# PMOD_ARD_RASP.net
KiCad netlist of a schematic drawn in Altium Designer
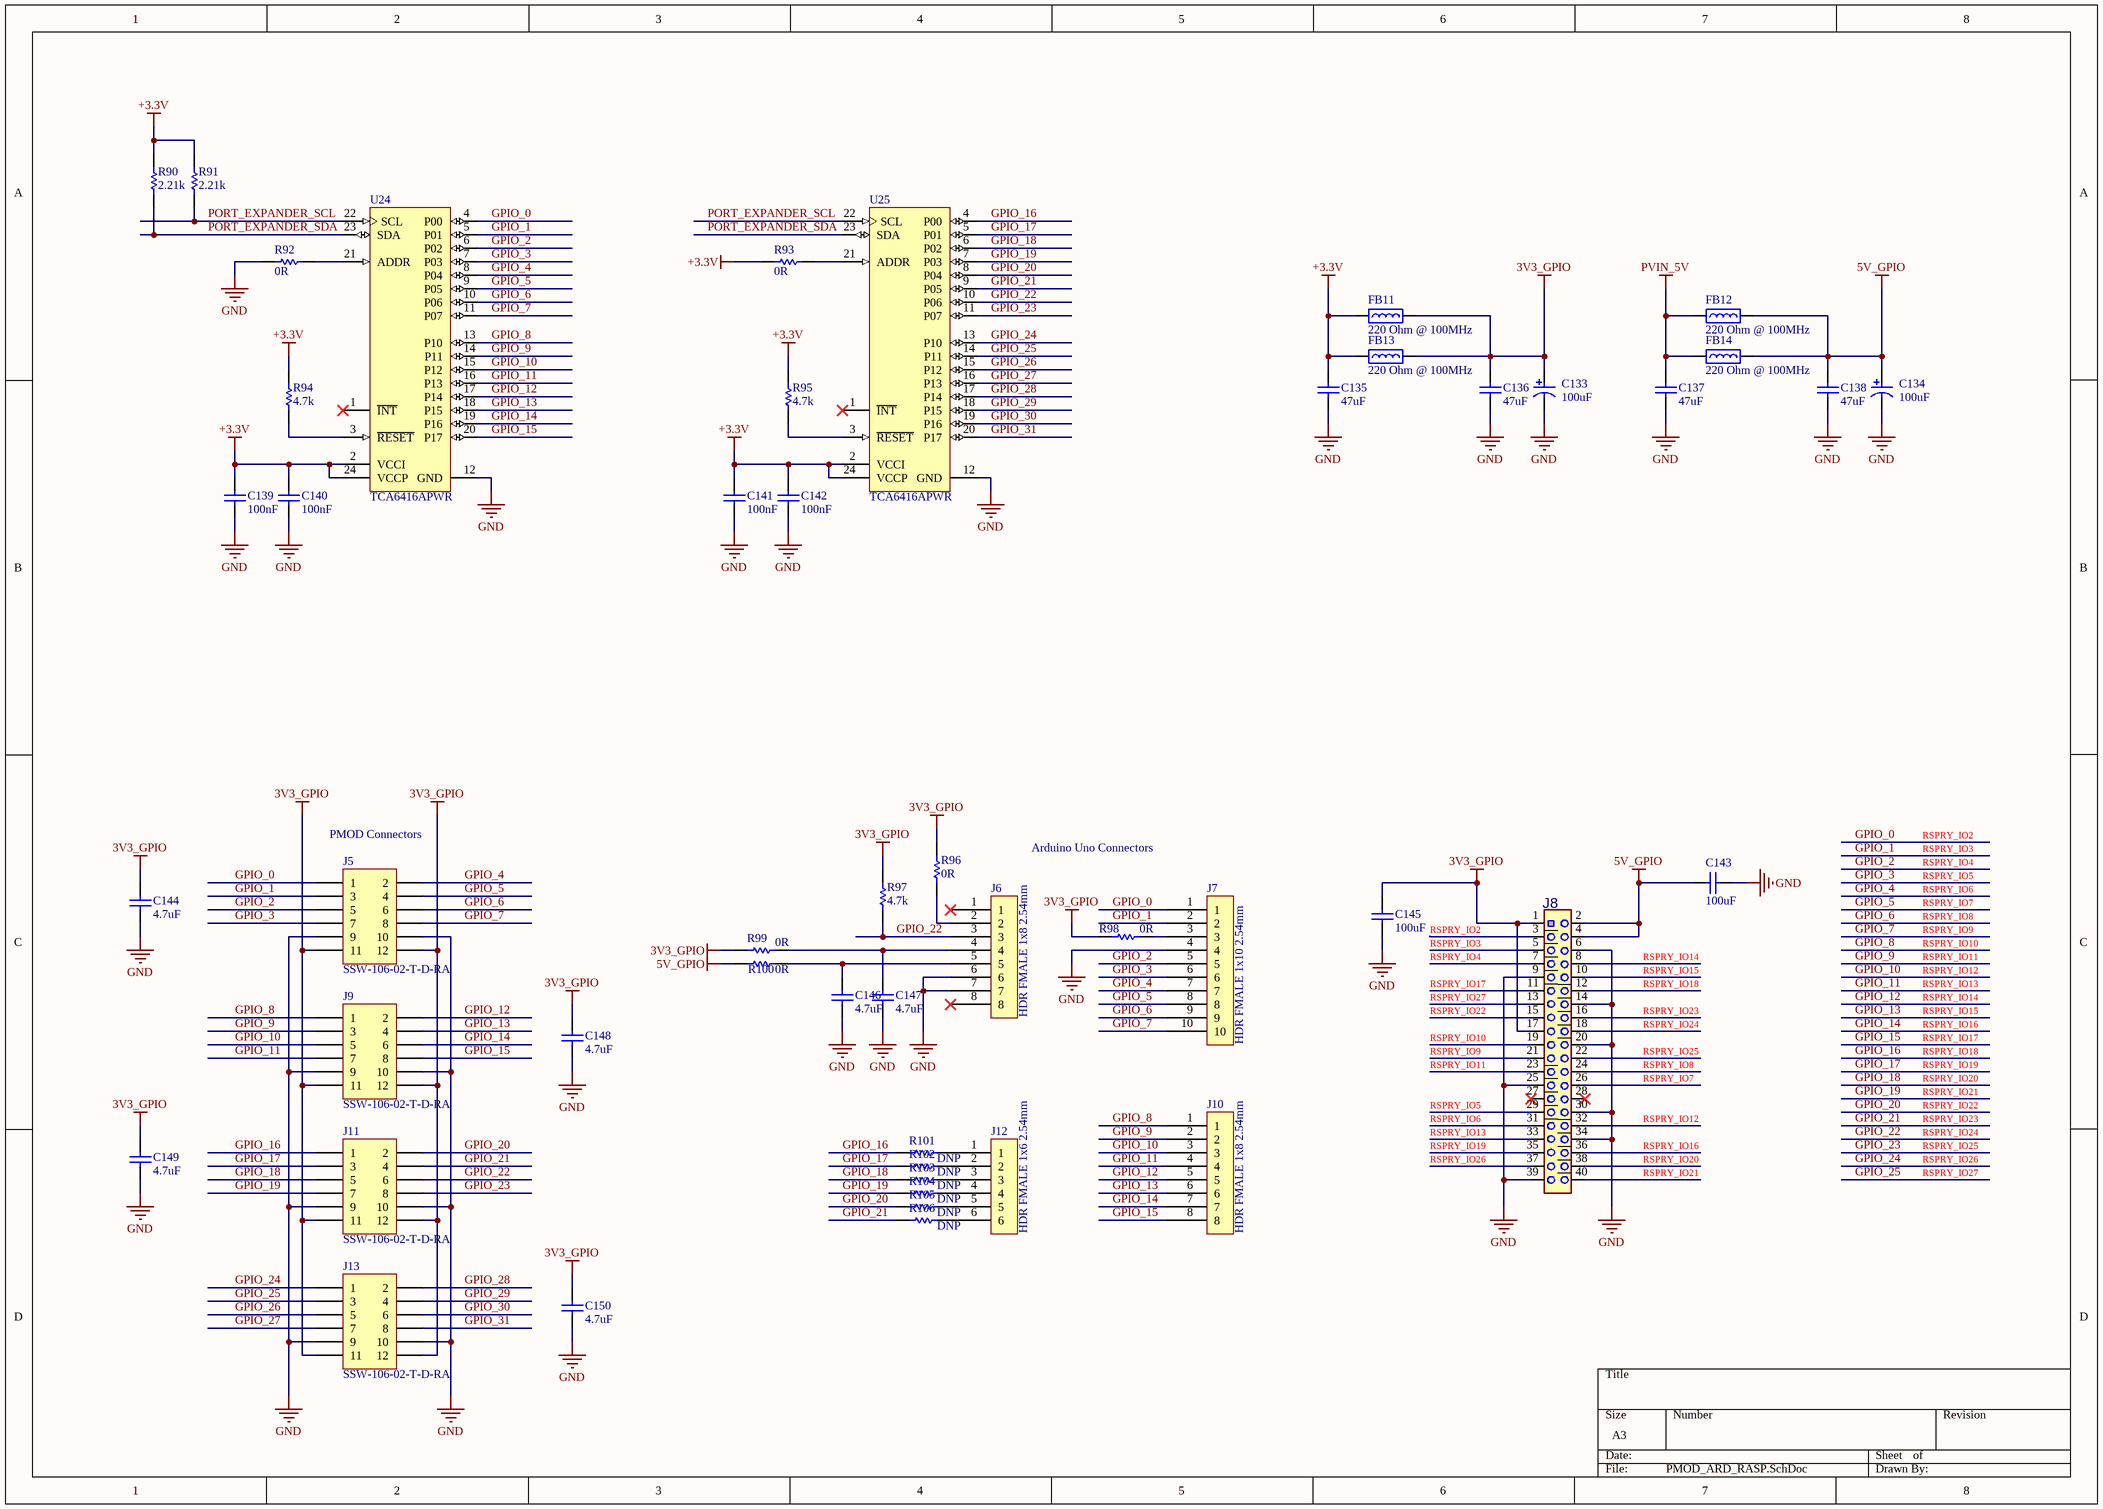
[diagram p0: PMOD_ARD_RASP.SchDoc]

(export (version "E")
  (design (tool "Eeschema 10.0.6"))
  (components
    (comp (ref "C133")
      (value "100uF")
      (footprint "AVX_TAN_F95_P_0905")
      (description "CAP TANT 100UF 6.3V 20% 0805")
      (fields (field (name "VOLTAGE") "6.3V") (field (name "TOLERANCE") "20%"))
      (libsource (lib "Ultrascale_SchLib") (part "CAPELE0905TAN100U6V3_20T"))
    )
    (comp (ref "C134")
      (value "100uF")
      (footprint "AVX_TAN_F95_P_0905")
      (description "CAP TANT 100UF 6.3V 20% 0805")
      (fields (field (name "VOLTAGE") "6.3V") (field (name "TOLERANCE") "20%"))
      (libsource (lib "Ultrascale_SchLib") (part "CAPELE0905TAN100U6V3_20T"))
    )
    (comp (ref "C135")
      (value "47uF")
      (footprint "CAPC3216L_1206")
      (description "CAP CER 47UF 25V X5R 1206")
      (fields (field (name "VOLTAGE") "25V") (field (name "TOLERANCE") "20%"))
      (libsource (lib "Ultrascale_SchLib") (part "CAPCER1206X5R47U25V_20T"))
    )
    (comp (ref "C136")
      (value "47uF")
      (footprint "CAPC3216L_1206")
      (description "CAP CER 47UF 25V X5R 1206")
      (fields (field (name "VOLTAGE") "25V") (field (name "TOLERANCE") "20%"))
      (libsource (lib "Ultrascale_SchLib") (part "CAPCER1206X5R47U25V_20T"))
    )
    (comp (ref "C137")
      (value "47uF")
      (footprint "CAPC3216L_1206")
      (description "CAP CER 47UF 25V X5R 1206")
      (fields (field (name "VOLTAGE") "25V") (field (name "TOLERANCE") "20%"))
      (libsource (lib "Ultrascale_SchLib") (part "CAPCER1206X5R47U25V_20T"))
    )
    (comp (ref "C138")
      (value "47uF")
      (footprint "CAPC3216L_1206")
      (description "CAP CER 47UF 25V X5R 1206")
      (fields (field (name "VOLTAGE") "25V") (field (name "TOLERANCE") "20%"))
      (libsource (lib "Ultrascale_SchLib") (part "CAPCER1206X5R47U25V_20T"))
    )
    (comp (ref "C139")
      (value "100nF")
      (footprint "CAPC1005L_0402")
      (description "CAP CER 0.1UF 25V X7R 0402")
      (fields (field (name "VOLTAGE") "25V") (field (name "TOLERANCE") "10%"))
      (libsource (lib "Ultrascale_SchLib") (part "CAPCER0402X7R100N25V_10T"))
    )
    (comp (ref "C140")
      (value "100nF")
      (footprint "CAPC1005L_0402")
      (description "CAP CER 0.1UF 25V X7R 0402")
      (fields (field (name "VOLTAGE") "25V") (field (name "TOLERANCE") "10%"))
      (libsource (lib "Ultrascale_SchLib") (part "CAPCER0402X7R100N25V_10T"))
    )
    (comp (ref "C141")
      (value "100nF")
      (footprint "CAPC1005L_0402")
      (description "CAP CER 0.1UF 25V X7R 0402")
      (fields (field (name "VOLTAGE") "25V") (field (name "TOLERANCE") "10%"))
      (libsource (lib "Ultrascale_SchLib") (part "CAPCER0402X7R100N25V_10T"))
    )
    (comp (ref "C142")
      (value "100nF")
      (footprint "CAPC1005L_0402")
      (description "CAP CER 0.1UF 25V X7R 0402")
      (fields (field (name "VOLTAGE") "25V") (field (name "TOLERANCE") "10%"))
      (libsource (lib "Ultrascale_SchLib") (part "CAPCER0402X7R100N25V_10T"))
    )
    (comp (ref "C143")
      (value "100uF")
      (footprint "CAPC3225N_1210")
      (description "CAP CER 100UF 16V X5R 1210")
      (fields (field (name "VOLTAGE") "16V") (field (name "TOLERANCE") "20%"))
      (libsource (lib "Ultrascale_SchLib") (part "CAPCER1210X5R100U16V_20T"))
    )
    (comp (ref "C144")
      (value "4.7uF")
      (footprint "CAPC1005L_0402")
      (description "CAP CER 4.7UF 10V X5R 0402")
      (fields (field (name "VOLTAGE") "10V") (field (name "TOLERANCE") "10%"))
      (libsource (lib "Ultrascale_SchLib") (part "CAPCER0402X5R4U710V_10T"))
    )
    (comp (ref "C145")
      (value "100uF")
      (footprint "CAPC3225N_1210")
      (description "CAP CER 100UF 16V X5R 1210")
      (fields (field (name "VOLTAGE") "16V") (field (name "TOLERANCE") "20%"))
      (libsource (lib "Ultrascale_SchLib") (part "CAPCER1210X5R100U16V_20T"))
    )
    (comp (ref "C146")
      (value "4.7uF")
      (footprint "CAPC1005L_0402")
      (description "CAP CER 4.7UF 10V X5R 0402")
      (fields (field (name "VOLTAGE") "10V") (field (name "TOLERANCE") "10%"))
      (libsource (lib "Ultrascale_SchLib") (part "CAPCER0402X5R4U710V_10T"))
    )
    (comp (ref "C147")
      (value "4.7uF")
      (footprint "CAPC1005L_0402")
      (description "CAP CER 4.7UF 10V X5R 0402")
      (fields (field (name "VOLTAGE") "10V") (field (name "TOLERANCE") "10%"))
      (libsource (lib "Ultrascale_SchLib") (part "CAPCER0402X5R4U710V_10T"))
    )
    (comp (ref "C148")
      (value "4.7uF")
      (footprint "CAPC1005L_0402")
      (description "CAP CER 4.7UF 10V X5R 0402")
      (fields (field (name "VOLTAGE") "10V") (field (name "TOLERANCE") "10%"))
      (libsource (lib "Ultrascale_SchLib") (part "CAPCER0402X5R4U710V_10T"))
    )
    (comp (ref "C149")
      (value "4.7uF")
      (footprint "CAPC1005L_0402")
      (description "CAP CER 4.7UF 10V X5R 0402")
      (fields (field (name "VOLTAGE") "10V") (field (name "TOLERANCE") "10%"))
      (libsource (lib "Ultrascale_SchLib") (part "CAPCER0402X5R4U710V_10T"))
    )
    (comp (ref "C150")
      (value "4.7uF")
      (footprint "CAPC1005L_0402")
      (description "CAP CER 4.7UF 10V X5R 0402")
      (fields (field (name "VOLTAGE") "10V") (field (name "TOLERANCE") "10%"))
      (libsource (lib "Ultrascale_SchLib") (part "CAPCER0402X5R4U710V_10T"))
    )
    (comp (ref "FB11")
      (value "BEAD0603_220_2A5_40M")
      (footprint "INDC1608N_0603")
      (description "FERRITE BEAD 220 OHM 0603 1LN")
      (fields (field (name "IMPEDANCE @ FREQUENCY") "220 Ohm @ 100MHz"))
      (libsource (lib "Ultrascale_SchLib") (part "BEAD0603_220_2A5_40M"))
    )
    (comp (ref "FB12")
      (value "BEAD0603_220_2A5_40M")
      (footprint "INDC1608N_0603")
      (description "FERRITE BEAD 220 OHM 0603 1LN")
      (fields (field (name "IMPEDANCE @ FREQUENCY") "220 Ohm @ 100MHz"))
      (libsource (lib "Ultrascale_SchLib") (part "BEAD0603_220_2A5_40M"))
    )
    (comp (ref "FB13")
      (value "BEAD0603_220_2A5_40M")
      (footprint "INDC1608N_0603")
      (description "FERRITE BEAD 220 OHM 0603 1LN")
      (fields (field (name "IMPEDANCE @ FREQUENCY") "220 Ohm @ 100MHz"))
      (libsource (lib "Ultrascale_SchLib") (part "BEAD0603_220_2A5_40M"))
    )
    (comp (ref "FB14")
      (value "BEAD0603_220_2A5_40M")
      (footprint "INDC1608N_0603")
      (description "FERRITE BEAD 220 OHM 0603 1LN")
      (fields (field (name "IMPEDANCE @ FREQUENCY") "220 Ohm @ 100MHz"))
      (libsource (lib "Ultrascale_SchLib") (part "BEAD0603_220_2A5_40M"))
    )
    (comp (ref "J5")
      (value "SSW-106-02-T-D-RA")
      (footprint "HDR2X6H")
      (description "CONN RCPT .100\" 12PS DL R/A TIN")
      (libsource (lib "Ultrascale_SchLib") (part "SSW-106-02-T-D-RA"))
    )
    (comp (ref "J6")
      (value "HDR FMALE 1x8 2.54mm")
      (footprint "Hdr_Female_1x8_2.54mm")
      (description "08-WAY SIL VERT SOCKET L/FREE")
      (fields
        (field (name ".CREATOR") "MM")
        (field (name ".CHECKED PCB") "RF")
        (field (name ".CHECKED SCH") "RF")
      )
      (libsource (lib "Ultrascale_SchLib") (part "M20-7820842"))
    )
    (comp (ref "J7")
      (value "HDR FMALE 1x10 2.54mm")
      (footprint "Hdr_Female_1x10_2.54mm")
      (description "10-WAY SIL VERT SOCKET L/FREE")
      (fields
        (field (name ".CREATOR") "MM")
        (field (name ".CHECKED PCB") "RF")
        (field (name ".CHECKED SCH") "RF")
      )
      (libsource (lib "Ultrascale_SchLib") (part "M20-7821046"))
    )
    (comp (ref "J8")
      (value "Header 2x20")
      (footprint "HDR_M_2.54_2x20")
      (description "CONN HEADER 40POS .100\" SGL GOLD")
      (libsource (lib "Ultrascale_SchLib") (part "Header 2x20"))
    )
    (comp (ref "J9")
      (value "SSW-106-02-T-D-RA")
      (footprint "HDR2X6H")
      (description "CONN RCPT .100\" 12PS DL R/A TIN")
      (libsource (lib "Ultrascale_SchLib") (part "SSW-106-02-T-D-RA"))
    )
    (comp (ref "J10")
      (value "HDR FMALE 1x8 2.54mm")
      (footprint "Hdr_Female_1x8_2.54mm")
      (description "08-WAY SIL VERT SOCKET L/FREE")
      (fields
        (field (name ".CREATOR") "MM")
        (field (name ".CHECKED PCB") "RF")
        (field (name ".CHECKED SCH") "RF")
      )
      (libsource (lib "Ultrascale_SchLib") (part "M20-7820842"))
    )
    (comp (ref "J11")
      (value "SSW-106-02-T-D-RA")
      (footprint "HDR2X6H")
      (description "CONN RCPT .100\" 12PS DL R/A TIN")
      (libsource (lib "Ultrascale_SchLib") (part "SSW-106-02-T-D-RA"))
    )
    (comp (ref "J12")
      (value "HDR FMALE 1x6 2.54mm")
      (footprint "Hdr_Female_1x6_2.54mm")
      (description "06-WAY SIL VERT SOCKET L/FREE")
      (fields
        (field (name ".CHECKED PCB") "MM")
        (field (name ".CHECKED SCH") "MM")
        (field (name ".CREATOR") "MM")
      )
      (libsource (lib "Ultrascale_SchLib") (part "M20-7820646"))
    )
    (comp (ref "J13")
      (value "SSW-106-02-T-D-RA")
      (footprint "HDR2X6H")
      (description "CONN RCPT .100\" 12PS DL R/A TIN")
      (libsource (lib "Ultrascale_SchLib") (part "SSW-106-02-T-D-RA"))
    )
    (comp (ref "R90")
      (value "2.21k")
      (footprint "RESC1005L_0402")
      (description "RES SMD 2.21K OHM 1% 1/10W 0402")
      (fields (field (name "POWER") "1/10W") (field (name "TOLERANCE") "1%"))
      (libsource (lib "Ultrascale_SchLib") (part "RES0402_2K21_0W1_1T"))
    )
    (comp (ref "R91")
      (value "2.21k")
      (footprint "RESC1005L_0402")
      (description "RES SMD 2.21K OHM 1% 1/10W 0402")
      (fields (field (name "POWER") "1/10W") (field (name "TOLERANCE") "1%"))
      (libsource (lib "Ultrascale_SchLib") (part "RES0402_2K21_0W1_1T"))
    )
    (comp (ref "R92")
      (value "0R")
      (footprint "RESC1005L_0402")
      (description "RES SMD 0 OHM JUMPER 1/10W 0402")
      (fields (field (name "POWER") "1/10W") (field (name "Comment") "RES0402_0R_0W1"))
      (libsource (lib "Ultrascale_SchLib") (part "RES0402_0R_0W1"))
    )
    (comp (ref "R93")
      (value "0R")
      (footprint "RESC1005L_0402")
      (description "RES SMD 0 OHM JUMPER 1/10W 0402")
      (fields (field (name "POWER") "1/10W") (field (name "Comment") "RES0402_0R_0W1"))
      (libsource (lib "Ultrascale_SchLib") (part "RES0402_0R_0W1"))
    )
    (comp (ref "R94")
      (value "4.7k")
      (footprint "RESC1005L_0402")
      (description "RES SMD 4.7K OHM 1% 1/10W 0402")
      (fields (field (name "POWER") "1/10W") (field (name "TOLERANCE") "1%"))
      (libsource (lib "Ultrascale_SchLib") (part "RES0402_4K7_0W1_1T"))
    )
    (comp (ref "R95")
      (value "4.7k")
      (footprint "RESC1005L_0402")
      (description "RES SMD 4.7K OHM 1% 1/10W 0402")
      (fields (field (name "POWER") "1/10W") (field (name "TOLERANCE") "1%"))
      (libsource (lib "Ultrascale_SchLib") (part "RES0402_4K7_0W1_1T"))
    )
    (comp (ref "R96")
      (value "0R")
      (footprint "RESC1005L_0402")
      (description "RES SMD 0 OHM JUMPER 1/16W 0402")
      (fields (field (name "POWER") "0.063W, 1/16W") (field (name "Comment") "RES0402_0R"))
      (libsource (lib "Ultrascale_SchLib") (part "RES0402_0R"))
    )
    (comp (ref "R97")
      (value "4.7k")
      (footprint "RESC1005L_0402")
      (description "RES SMD 4.7K OHM 1% 1/10W 0402")
      (fields (field (name "POWER") "1/10W") (field (name "TOLERANCE") "1%"))
      (libsource (lib "Ultrascale_SchLib") (part "RES0402_4K7_0W1_1T"))
    )
    (comp (ref "R98")
      (value "0R")
      (footprint "RESC1005L_0402")
      (description "RES SMD 0 OHM JUMPER 1/16W 0402")
      (fields (field (name "POWER") "0.063W, 1/16W") (field (name "Comment") "RES0402_0R"))
      (libsource (lib "Ultrascale_SchLib") (part "RES0402_0R"))
    )
    (comp (ref "R99")
      (value "0R")
      (footprint "RESC1005L_0402")
      (description "RES SMD 0 OHM JUMPER 1/16W 0402")
      (fields (field (name "POWER") "0.063W, 1/16W") (field (name "Comment") "RES0402_0R"))
      (libsource (lib "Ultrascale_SchLib") (part "RES0402_0R"))
    )
    (comp (ref "R100")
      (value "0R")
      (footprint "RESC1005L_0402")
      (description "RES SMD 0 OHM JUMPER 1/16W 0402")
      (fields (field (name "POWER") "0.063W, 1/16W") (field (name "Comment") "RES0402_0R"))
      (libsource (lib "Ultrascale_SchLib") (part "RES0402_0R"))
    )
    (comp (ref "R101")
      (value "DNP")
      (footprint "RESC1005L_0402")
      (description "RES SMD 0402 Footprint")
      (fields (field (name "Comment") "RES0402"))
      (libsource (lib "Ultrascale_SchLib") (part "RES0402"))
    )
    (comp (ref "R102")
      (value "DNP")
      (footprint "RESC1005L_0402")
      (description "RES SMD 0402 Footprint")
      (fields (field (name "Comment") "RES0402"))
      (libsource (lib "Ultrascale_SchLib") (part "RES0402"))
    )
    (comp (ref "R103")
      (value "DNP")
      (footprint "RESC1005L_0402")
      (description "RES SMD 0402 Footprint")
      (fields (field (name "Comment") "RES0402"))
      (libsource (lib "Ultrascale_SchLib") (part "RES0402"))
    )
    (comp (ref "R104")
      (value "DNP")
      (footprint "RESC1005L_0402")
      (description "RES SMD 0402 Footprint")
      (fields (field (name "Comment") "RES0402"))
      (libsource (lib "Ultrascale_SchLib") (part "RES0402"))
    )
    (comp (ref "R105")
      (value "DNP")
      (footprint "RESC1005L_0402")
      (description "RES SMD 0402 Footprint")
      (fields (field (name "Comment") "RES0402"))
      (libsource (lib "Ultrascale_SchLib") (part "RES0402"))
    )
    (comp (ref "R106")
      (value "DNP")
      (footprint "RESC1005L_0402")
      (description "RES SMD 0402 Footprint")
      (fields (field (name "Comment") "RES0402"))
      (libsource (lib "Ultrascale_SchLib") (part "RES0402"))
    )
    (comp (ref "U24")
      (value "TCA6416APWR")
      (footprint "PW24_L")
      (fields (field (name "MANUFACTURER") "Texas Instruments"))
      (libsource (lib "Ultrascale_SchLib") (part "TCA6416APWR"))
    )
    (comp (ref "U25")
      (value "TCA6416APWR")
      (footprint "PW24_L")
      (fields (field (name "MANUFACTURER") "Texas Instruments"))
      (libsource (lib "Ultrascale_SchLib") (part "TCA6416APWR"))
    )
  )
  (nets
    (net (code "1") (name "+3.3V") (class "Default")
      (node (ref "C135") (pin "2") (pinfunction "2_2") (pintype "passive"))
      (node (ref "C139") (pin "2") (pinfunction "2_2") (pintype "passive"))
      (node (ref "C140") (pin "2") (pinfunction "2_2") (pintype "passive"))
      (node (ref "C141") (pin "2") (pinfunction "2_2") (pintype "passive"))
      (node (ref "C142") (pin "2") (pinfunction "2_2") (pintype "passive"))
      (node (ref "FB11") (pin "1") (pinfunction "1_1") (pintype "passive"))
      (node (ref "FB13") (pin "1") (pinfunction "1_1") (pintype "passive"))
      (node (ref "R90") (pin "2") (pinfunction "2_2") (pintype "passive"))
      (node (ref "R91") (pin "2") (pinfunction "2_2") (pintype "passive"))
      (node (ref "R93") (pin "1") (pinfunction "1_1") (pintype "passive"))
      (node (ref "R94") (pin "2") (pinfunction "2_2") (pintype "passive"))
      (node (ref "R95") (pin "2") (pinfunction "2_2") (pintype "passive"))
      (node (ref "U24") (pin "2") (pinfunction "VCCI_2") (pintype "power_in"))
      (node (ref "U24") (pin "24") (pinfunction "VCCP_24") (pintype "power_in"))
      (node (ref "U25") (pin "2") (pinfunction "VCCI_2") (pintype "power_in"))
      (node (ref "U25") (pin "24") (pinfunction "VCCP_24") (pintype "power_in"))
    )
    (net (code "2") (name "/GPIO_0") (class "Default")
      (node (ref "J5") (pin "1") (pinfunction "1_1") (pintype "passive"))
      (node (ref "J7") (pin "1") (pinfunction "1_1") (pintype "passive"))
      (node (ref "J8") (pin "3") (pinfunction "P3_3") (pintype "passive"))
      (node (ref "U24") (pin "4") (pinfunction "P00_4") (pintype "bidirectional"))
    )
    (net (code "3") (name "/GPIO_1") (class "Default")
      (node (ref "J5") (pin "3") (pinfunction "3_3") (pintype "passive"))
      (node (ref "J7") (pin "2") (pinfunction "2_2") (pintype "passive"))
      (node (ref "J8") (pin "5") (pinfunction "P5_5") (pintype "passive"))
      (node (ref "U24") (pin "5") (pinfunction "P01_5") (pintype "bidirectional"))
    )
    (net (code "4") (name "/GPIO_2") (class "Default")
      (node (ref "J5") (pin "5") (pinfunction "5_5") (pintype "passive"))
      (node (ref "J7") (pin "5") (pinfunction "5_5") (pintype "passive"))
      (node (ref "J8") (pin "7") (pinfunction "P7_7") (pintype "passive"))
      (node (ref "U24") (pin "6") (pinfunction "P02_6") (pintype "bidirectional"))
    )
    (net (code "5") (name "/GPIO_3") (class "Default")
      (node (ref "J5") (pin "7") (pinfunction "7_7") (pintype "passive"))
      (node (ref "J7") (pin "6") (pinfunction "6_6") (pintype "passive"))
      (node (ref "J8") (pin "29") (pinfunction "P29_29") (pintype "passive"))
      (node (ref "U24") (pin "7") (pinfunction "P03_7") (pintype "bidirectional"))
    )
    (net (code "6") (name "/GPIO_4") (class "Default")
      (node (ref "J5") (pin "2") (pinfunction "2_2") (pintype "passive"))
      (node (ref "J7") (pin "7") (pinfunction "7_7") (pintype "passive"))
      (node (ref "J8") (pin "31") (pinfunction "P31_31") (pintype "passive"))
      (node (ref "U24") (pin "8") (pinfunction "P04_8") (pintype "bidirectional"))
    )
    (net (code "7") (name "/GPIO_5") (class "Default")
      (node (ref "J5") (pin "4") (pinfunction "4_4") (pintype "passive"))
      (node (ref "J7") (pin "8") (pinfunction "8_8") (pintype "passive"))
      (node (ref "J8") (pin "26") (pinfunction "P26_26") (pintype "passive"))
      (node (ref "U24") (pin "9") (pinfunction "P05_9") (pintype "bidirectional"))
    )
    (net (code "8") (name "/GPIO_6") (class "Default")
      (node (ref "J5") (pin "6") (pinfunction "6_6") (pintype "passive"))
      (node (ref "J7") (pin "9") (pinfunction "9_9") (pintype "passive"))
      (node (ref "J8") (pin "24") (pinfunction "P24_24") (pintype "passive"))
      (node (ref "U24") (pin "10") (pinfunction "P06_10") (pintype "bidirectional"))
    )
    (net (code "9") (name "/GPIO_7") (class "Default")
      (node (ref "J5") (pin "8") (pinfunction "8_8") (pintype "passive"))
      (node (ref "J7") (pin "10") (pinfunction "10_10") (pintype "passive"))
      (node (ref "J8") (pin "21") (pinfunction "P21_21") (pintype "passive"))
      (node (ref "U24") (pin "11") (pinfunction "P07_11") (pintype "bidirectional"))
    )
    (net (code "10") (name "/GPIO_8") (class "Default")
      (node (ref "J10") (pin "1") (pinfunction "1_1") (pintype "passive"))
      (node (ref "J8") (pin "19") (pinfunction "P19_19") (pintype "passive"))
      (node (ref "J9") (pin "1") (pinfunction "1_1") (pintype "passive"))
      (node (ref "U24") (pin "13") (pinfunction "P10_13") (pintype "bidirectional"))
    )
    (net (code "11") (name "/GPIO_9") (class "Default")
      (node (ref "J10") (pin "2") (pinfunction "2_2") (pintype "passive"))
      (node (ref "J8") (pin "23") (pinfunction "P23_23") (pintype "passive"))
      (node (ref "J9") (pin "3") (pinfunction "3_3") (pintype "passive"))
      (node (ref "U24") (pin "14") (pinfunction "P11_14") (pintype "bidirectional"))
    )
    (net (code "12") (name "/GPIO_10") (class "Default")
      (node (ref "J10") (pin "3") (pinfunction "3_3") (pintype "passive"))
      (node (ref "J8") (pin "32") (pinfunction "P32_32") (pintype "passive"))
      (node (ref "J9") (pin "5") (pinfunction "5_5") (pintype "passive"))
      (node (ref "U24") (pin "15") (pinfunction "P12_15") (pintype "bidirectional"))
    )
    (net (code "13") (name "/GPIO_11") (class "Default")
      (node (ref "J10") (pin "4") (pinfunction "4_4") (pintype "passive"))
      (node (ref "J8") (pin "33") (pinfunction "P33_33") (pintype "passive"))
      (node (ref "J9") (pin "7") (pinfunction "7_7") (pintype "passive"))
      (node (ref "U24") (pin "16") (pinfunction "P13_16") (pintype "bidirectional"))
    )
    (net (code "14") (name "/GPIO_12") (class "Default")
      (node (ref "J10") (pin "5") (pinfunction "5_5") (pintype "passive"))
      (node (ref "J8") (pin "8") (pinfunction "P8_8") (pintype "passive"))
      (node (ref "J9") (pin "2") (pinfunction "2_2") (pintype "passive"))
      (node (ref "U24") (pin "17") (pinfunction "P14_17") (pintype "bidirectional"))
    )
    (net (code "15") (name "/GPIO_13") (class "Default")
      (node (ref "J10") (pin "6") (pinfunction "6_6") (pintype "passive"))
      (node (ref "J8") (pin "10") (pinfunction "P10_10") (pintype "passive"))
      (node (ref "J9") (pin "4") (pinfunction "4_4") (pintype "passive"))
      (node (ref "U24") (pin "18") (pinfunction "P15_18") (pintype "bidirectional"))
    )
    (net (code "16") (name "/GPIO_14") (class "Default")
      (node (ref "J10") (pin "7") (pinfunction "7_7") (pintype "passive"))
      (node (ref "J8") (pin "36") (pinfunction "P36_36") (pintype "passive"))
      (node (ref "J9") (pin "6") (pinfunction "6_6") (pintype "passive"))
      (node (ref "U24") (pin "19") (pinfunction "P16_19") (pintype "bidirectional"))
    )
    (net (code "17") (name "/GPIO_15") (class "Default")
      (node (ref "J10") (pin "8") (pinfunction "8_8") (pintype "passive"))
      (node (ref "J8") (pin "11") (pinfunction "P11_11") (pintype "passive"))
      (node (ref "J9") (pin "8") (pinfunction "8_8") (pintype "passive"))
      (node (ref "U24") (pin "20") (pinfunction "P17_20") (pintype "bidirectional"))
    )
    (net (code "18") (name "/GPIO_16") (class "Default")
      (node (ref "J11") (pin "1") (pinfunction "1_1") (pintype "passive"))
      (node (ref "J8") (pin "12") (pinfunction "P12_12") (pintype "passive"))
      (node (ref "R101") (pin "1") (pinfunction "1_1") (pintype "passive"))
      (node (ref "U25") (pin "4") (pinfunction "P00_4") (pintype "bidirectional"))
    )
    (net (code "19") (name "/GPIO_17") (class "Default")
      (node (ref "J11") (pin "3") (pinfunction "3_3") (pintype "passive"))
      (node (ref "J8") (pin "35") (pinfunction "P35_35") (pintype "passive"))
      (node (ref "R102") (pin "1") (pinfunction "1_1") (pintype "passive"))
      (node (ref "U25") (pin "5") (pinfunction "P01_5") (pintype "bidirectional"))
    )
    (net (code "20") (name "/GPIO_18") (class "Default")
      (node (ref "J11") (pin "5") (pinfunction "5_5") (pintype "passive"))
      (node (ref "J8") (pin "38") (pinfunction "P38_38") (pintype "passive"))
      (node (ref "R103") (pin "1") (pinfunction "1_1") (pintype "passive"))
      (node (ref "U25") (pin "6") (pinfunction "P02_6") (pintype "bidirectional"))
    )
    (net (code "21") (name "/GPIO_19") (class "Default")
      (node (ref "J11") (pin "7") (pinfunction "7_7") (pintype "passive"))
      (node (ref "J8") (pin "40") (pinfunction "P40_40") (pintype "passive"))
      (node (ref "R104") (pin "1") (pinfunction "1_1") (pintype "passive"))
      (node (ref "U25") (pin "7") (pinfunction "P03_7") (pintype "bidirectional"))
    )
    (net (code "22") (name "/GPIO_20") (class "Default")
      (node (ref "J11") (pin "2") (pinfunction "2_2") (pintype "passive"))
      (node (ref "J8") (pin "15") (pinfunction "P15_15") (pintype "passive"))
      (node (ref "R105") (pin "1") (pinfunction "1_1") (pintype "passive"))
      (node (ref "U25") (pin "8") (pinfunction "P04_8") (pintype "bidirectional"))
    )
    (net (code "23") (name "/GPIO_21") (class "Default")
      (node (ref "J11") (pin "4") (pinfunction "4_4") (pintype "passive"))
      (node (ref "J8") (pin "16") (pinfunction "P16_16") (pintype "passive"))
      (node (ref "R106") (pin "1") (pinfunction "1_1") (pintype "passive"))
      (node (ref "U25") (pin "9") (pinfunction "P05_9") (pintype "bidirectional"))
    )
    (net (code "24") (name "/GPIO_22") (class "Default")
      (node (ref "J11") (pin "6") (pinfunction "6_6") (pintype "passive"))
      (node (ref "J6") (pin "3") (pinfunction "3_3") (pintype "passive"))
      (node (ref "J8") (pin "18") (pinfunction "P18_18") (pintype "passive"))
      (node (ref "R97") (pin "1") (pinfunction "1_1") (pintype "passive"))
      (node (ref "U25") (pin "10") (pinfunction "P06_10") (pintype "bidirectional"))
    )
    (net (code "25") (name "/GPIO_23") (class "Default")
      (node (ref "J11") (pin "8") (pinfunction "8_8") (pintype "passive"))
      (node (ref "J8") (pin "22") (pinfunction "P22_22") (pintype "passive"))
      (node (ref "U25") (pin "11") (pinfunction "P07_11") (pintype "bidirectional"))
    )
    (net (code "26") (name "/GPIO_24") (class "Default")
      (node (ref "J13") (pin "1") (pinfunction "1_1") (pintype "passive"))
      (node (ref "J8") (pin "37") (pinfunction "P37_37") (pintype "passive"))
      (node (ref "U25") (pin "13") (pinfunction "P10_13") (pintype "bidirectional"))
    )
    (net (code "27") (name "/GPIO_25") (class "Default")
      (node (ref "J13") (pin "3") (pinfunction "3_3") (pintype "passive"))
      (node (ref "J8") (pin "13") (pinfunction "P13_13") (pintype "passive"))
      (node (ref "U25") (pin "14") (pinfunction "P11_14") (pintype "bidirectional"))
    )
    (net (code "28") (name "/GPIO_26") (class "Default")
      (node (ref "J13") (pin "5") (pinfunction "5_5") (pintype "passive"))
      (node (ref "U25") (pin "15") (pinfunction "P12_15") (pintype "bidirectional"))
    )
    (net (code "29") (name "/GPIO_27") (class "Default")
      (node (ref "J13") (pin "7") (pinfunction "7_7") (pintype "passive"))
      (node (ref "U25") (pin "16") (pinfunction "P13_16") (pintype "bidirectional"))
    )
    (net (code "30") (name "/GPIO_28") (class "Default")
      (node (ref "J13") (pin "2") (pinfunction "2_2") (pintype "passive"))
      (node (ref "U25") (pin "17") (pinfunction "P14_17") (pintype "bidirectional"))
    )
    (net (code "31") (name "/GPIO_29") (class "Default")
      (node (ref "J13") (pin "4") (pinfunction "4_4") (pintype "passive"))
      (node (ref "U25") (pin "18") (pinfunction "P15_18") (pintype "bidirectional"))
    )
    (net (code "32") (name "/GPIO_30") (class "Default")
      (node (ref "J13") (pin "6") (pinfunction "6_6") (pintype "passive"))
      (node (ref "U25") (pin "19") (pinfunction "P16_19") (pintype "bidirectional"))
    )
    (net (code "33") (name "/GPIO_31") (class "Default")
      (node (ref "J13") (pin "8") (pinfunction "8_8") (pintype "passive"))
      (node (ref "U25") (pin "20") (pinfunction "P17_20") (pintype "bidirectional"))
    )
    (net (code "34") (name "/PORT_EXPANDER_SCL") (class "Default")
      (node (ref "R91") (pin "1") (pinfunction "1_1") (pintype "passive"))
      (node (ref "U24") (pin "22") (pinfunction "SCL_22") (pintype "input"))
      (node (ref "U25") (pin "22") (pinfunction "SCL_22") (pintype "input"))
    )
    (net (code "35") (name "/PORT_EXPANDER_SDA") (class "Default")
      (node (ref "R90") (pin "1") (pinfunction "1_1") (pintype "passive"))
      (node (ref "U24") (pin "23") (pinfunction "SDA_23") (pintype "bidirectional"))
      (node (ref "U25") (pin "23") (pinfunction "SDA_23") (pintype "bidirectional"))
    )
    (net (code "36") (name "3V3_GPIO") (class "Default")
      (node (ref "C133") (pin "1") (pinfunction "1_1") (pintype "passive"))
      (node (ref "C136") (pin "2") (pinfunction "2_2") (pintype "passive"))
      (node (ref "C144") (pin "2") (pinfunction "2_2") (pintype "passive"))
      (node (ref "C145") (pin "2") (pinfunction "2_2") (pintype "passive"))
      (node (ref "C148") (pin "2") (pinfunction "2_2") (pintype "passive"))
      (node (ref "C149") (pin "2") (pinfunction "2_2") (pintype "passive"))
      (node (ref "C150") (pin "2") (pinfunction "2_2") (pintype "passive"))
      (node (ref "FB11") (pin "2") (pinfunction "2_2") (pintype "passive"))
      (node (ref "FB13") (pin "2") (pinfunction "2_2") (pintype "passive"))
      (node (ref "J11") (pin "11") (pinfunction "11_11") (pintype "passive"))
      (node (ref "J11") (pin "12") (pinfunction "12_12") (pintype "passive"))
      (node (ref "J13") (pin "11") (pinfunction "11_11") (pintype "passive"))
      (node (ref "J13") (pin "12") (pinfunction "12_12") (pintype "passive"))
      (node (ref "J5") (pin "11") (pinfunction "11_11") (pintype "passive"))
      (node (ref "J5") (pin "12") (pinfunction "12_12") (pintype "passive"))
      (node (ref "J8") (pin "1") (pinfunction "P1_1") (pintype "passive"))
      (node (ref "J8") (pin "17") (pinfunction "P17_17") (pintype "passive"))
      (node (ref "J9") (pin "11") (pinfunction "11_11") (pintype "passive"))
      (node (ref "J9") (pin "12") (pinfunction "12_12") (pintype "passive"))
      (node (ref "R96") (pin "1") (pinfunction "1_1") (pintype "passive"))
      (node (ref "R97") (pin "2") (pinfunction "2_2") (pintype "passive"))
      (node (ref "R98") (pin "2") (pinfunction "2_2") (pintype "passive"))
      (node (ref "R99") (pin "2") (pinfunction "2_2") (pintype "passive"))
    )
    (net (code "37") (name "5V_GPIO") (class "Default")
      (node (ref "C134") (pin "1") (pinfunction "1_1") (pintype "passive"))
      (node (ref "C138") (pin "2") (pinfunction "2_2") (pintype "passive"))
      (node (ref "C143") (pin "2") (pinfunction "2_2") (pintype "passive"))
      (node (ref "FB12") (pin "2") (pinfunction "2_2") (pintype "passive"))
      (node (ref "FB14") (pin "2") (pinfunction "2_2") (pintype "passive"))
      (node (ref "J8") (pin "2") (pinfunction "P2_2") (pintype "passive"))
      (node (ref "J8") (pin "4") (pinfunction "P4_4") (pintype "passive"))
      (node (ref "R100") (pin "2") (pinfunction "2_2") (pintype "passive"))
    )
    (net (code "38") (name "GND") (class "Default")
      (node (ref "C133") (pin "2") (pinfunction "2_2") (pintype "passive"))
      (node (ref "C134") (pin "2") (pinfunction "2_2") (pintype "passive"))
      (node (ref "C135") (pin "1") (pinfunction "1_1") (pintype "passive"))
      (node (ref "C136") (pin "1") (pinfunction "1_1") (pintype "passive"))
      (node (ref "C137") (pin "1") (pinfunction "1_1") (pintype "passive"))
      (node (ref "C138") (pin "1") (pinfunction "1_1") (pintype "passive"))
      (node (ref "C139") (pin "1") (pinfunction "1_1") (pintype "passive"))
      (node (ref "C140") (pin "1") (pinfunction "1_1") (pintype "passive"))
      (node (ref "C141") (pin "1") (pinfunction "1_1") (pintype "passive"))
      (node (ref "C142") (pin "1") (pinfunction "1_1") (pintype "passive"))
      (node (ref "C143") (pin "1") (pinfunction "1_1") (pintype "passive"))
      (node (ref "C144") (pin "1") (pinfunction "1_1") (pintype "passive"))
      (node (ref "C145") (pin "1") (pinfunction "1_1") (pintype "passive"))
      (node (ref "C146") (pin "1") (pinfunction "1_1") (pintype "passive"))
      (node (ref "C147") (pin "1") (pinfunction "1_1") (pintype "passive"))
      (node (ref "C148") (pin "1") (pinfunction "1_1") (pintype "passive"))
      (node (ref "C149") (pin "1") (pinfunction "1_1") (pintype "passive"))
      (node (ref "C150") (pin "1") (pinfunction "1_1") (pintype "passive"))
      (node (ref "J11") (pin "10") (pinfunction "10_10") (pintype "passive"))
      (node (ref "J11") (pin "9") (pinfunction "9_9") (pintype "passive"))
      (node (ref "J13") (pin "10") (pinfunction "10_10") (pintype "passive"))
      (node (ref "J13") (pin "9") (pinfunction "9_9") (pintype "passive"))
      (node (ref "J5") (pin "10") (pinfunction "10_10") (pintype "passive"))
      (node (ref "J5") (pin "9") (pinfunction "9_9") (pintype "passive"))
      (node (ref "J6") (pin "6") (pinfunction "6_6") (pintype "passive"))
      (node (ref "J6") (pin "7") (pinfunction "7_7") (pintype "passive"))
      (node (ref "J7") (pin "4") (pinfunction "4_4") (pintype "passive"))
      (node (ref "J8") (pin "14") (pinfunction "P14_14") (pintype "passive"))
      (node (ref "J8") (pin "20") (pinfunction "P20_20") (pintype "passive"))
      (node (ref "J8") (pin "25") (pinfunction "P25_25") (pintype "passive"))
      (node (ref "J8") (pin "30") (pinfunction "P30_30") (pintype "passive"))
      (node (ref "J8") (pin "34") (pinfunction "P34_34") (pintype "passive"))
      (node (ref "J8") (pin "39") (pinfunction "P39_39") (pintype "passive"))
      (node (ref "J8") (pin "6") (pinfunction "P6_6") (pintype "passive"))
      (node (ref "J8") (pin "9") (pinfunction "P9_9") (pintype "passive"))
      (node (ref "J9") (pin "10") (pinfunction "10_10") (pintype "passive"))
      (node (ref "J9") (pin "9") (pinfunction "9_9") (pintype "passive"))
      (node (ref "R92") (pin "1") (pinfunction "1_1") (pintype "passive"))
      (node (ref "U24") (pin "12") (pinfunction "GND_12") (pintype "power_in"))
      (node (ref "U25") (pin "12") (pinfunction "GND_12") (pintype "power_in"))
    )
    (net (code "39") (name "Net-(C146-Pad2)") (class "Default")
      (node (ref "C146") (pin "2") (pinfunction "2_2") (pintype "passive"))
      (node (ref "J6") (pin "5") (pinfunction "5_5") (pintype "passive"))
      (node (ref "R100") (pin "1") (pinfunction "1_1") (pintype "passive"))
    )
    (net (code "40") (name "Net-(C147-Pad2)") (class "Default")
      (node (ref "C147") (pin "2") (pinfunction "2_2") (pintype "passive"))
      (node (ref "J6") (pin "4") (pinfunction "4_4") (pintype "passive"))
      (node (ref "R99") (pin "1") (pinfunction "1_1") (pintype "passive"))
    )
    (net (code "41") (name "Net-(J6-Pad2)") (class "Default")
      (node (ref "J6") (pin "2") (pinfunction "2_2") (pintype "passive"))
      (node (ref "R96") (pin "2") (pinfunction "2_2") (pintype "passive"))
    )
    (net (code "42") (name "Net-(J7-Pad3)") (class "Default")
      (node (ref "J7") (pin "3") (pinfunction "3_3") (pintype "passive"))
      (node (ref "R98") (pin "1") (pinfunction "1_1") (pintype "passive"))
    )
    (net (code "43") (name "Net-(J12-Pad1)") (class "Default")
      (node (ref "J12") (pin "1") (pinfunction "1_1") (pintype "passive"))
      (node (ref "R101") (pin "2") (pinfunction "2_2") (pintype "passive"))
    )
    (net (code "44") (name "Net-(J12-Pad2)") (class "Default")
      (node (ref "J12") (pin "2") (pinfunction "2_2") (pintype "passive"))
      (node (ref "R102") (pin "2") (pinfunction "2_2") (pintype "passive"))
    )
    (net (code "45") (name "Net-(J12-Pad3)") (class "Default")
      (node (ref "J12") (pin "3") (pinfunction "3_3") (pintype "passive"))
      (node (ref "R103") (pin "2") (pinfunction "2_2") (pintype "passive"))
    )
    (net (code "46") (name "Net-(J12-Pad4)") (class "Default")
      (node (ref "J12") (pin "4") (pinfunction "4_4") (pintype "passive"))
      (node (ref "R104") (pin "2") (pinfunction "2_2") (pintype "passive"))
    )
    (net (code "47") (name "Net-(J12-Pad5)") (class "Default")
      (node (ref "J12") (pin "5") (pinfunction "5_5") (pintype "passive"))
      (node (ref "R105") (pin "2") (pinfunction "2_2") (pintype "passive"))
    )
    (net (code "48") (name "Net-(J12-Pad6)") (class "Default")
      (node (ref "J12") (pin "6") (pinfunction "6_6") (pintype "passive"))
      (node (ref "R106") (pin "2") (pinfunction "2_2") (pintype "passive"))
    )
    (net (code "49") (name "Net-(U24-ADDR)") (class "Default")
      (node (ref "R92") (pin "2") (pinfunction "2_2") (pintype "passive"))
      (node (ref "U24") (pin "21") (pinfunction "ADDR_21") (pintype "input"))
    )
    (net (code "50") (name "Net-(U24-~{RESET})") (class "Default")
      (node (ref "R94") (pin "1") (pinfunction "1_1") (pintype "passive"))
      (node (ref "U24") (pin "3") (pinfunction "~{RESET}_3") (pintype "input"))
    )
    (net (code "51") (name "Net-(U25-ADDR)") (class "Default")
      (node (ref "R93") (pin "2") (pinfunction "2_2") (pintype "passive"))
      (node (ref "U25") (pin "21") (pinfunction "ADDR_21") (pintype "input"))
    )
    (net (code "52") (name "Net-(U25-~{RESET})") (class "Default")
      (node (ref "R95") (pin "1") (pinfunction "1_1") (pintype "passive"))
      (node (ref "U25") (pin "3") (pinfunction "~{RESET}_3") (pintype "input"))
    )
    (net (code "53") (name "PVIN_5V") (class "Default")
      (node (ref "C137") (pin "2") (pinfunction "2_2") (pintype "passive"))
      (node (ref "FB12") (pin "1") (pinfunction "1_1") (pintype "passive"))
      (node (ref "FB14") (pin "1") (pinfunction "1_1") (pintype "passive"))
    )
    (net (code "54") (name "unconnected-(J6-Pad1)") (class "Default")
      (node (ref "J6") (pin "1") (pinfunction "1_1") (pintype "passive+no_connect"))
    )
    (net (code "55") (name "unconnected-(J6-Pad8)") (class "Default")
      (node (ref "J6") (pin "8") (pinfunction "8_8") (pintype "passive+no_connect"))
    )
    (net (code "56") (name "unconnected-(J8-P27-Pad27)") (class "Default")
      (node (ref "J8") (pin "27") (pinfunction "P27_27") (pintype "passive+no_connect"))
    )
    (net (code "57") (name "unconnected-(J8-P28-Pad28)") (class "Default")
      (node (ref "J8") (pin "28") (pinfunction "P28_28") (pintype "passive+no_connect"))
    )
    (net (code "58") (name "unconnected-(U24-~{INT}-Pad1)") (class "Default")
      (node (ref "U24") (pin "1") (pinfunction "~{INT}_1") (pintype "open_collector+no_connect"))
    )
    (net (code "59") (name "unconnected-(U25-~{INT}-Pad1)") (class "Default")
      (node (ref "U25") (pin "1") (pinfunction "~{INT}_1") (pintype "open_collector+no_connect"))
    )
  )
)
